# Side_1P.net
KiCad netlist of a schematic drawn in EAGLE
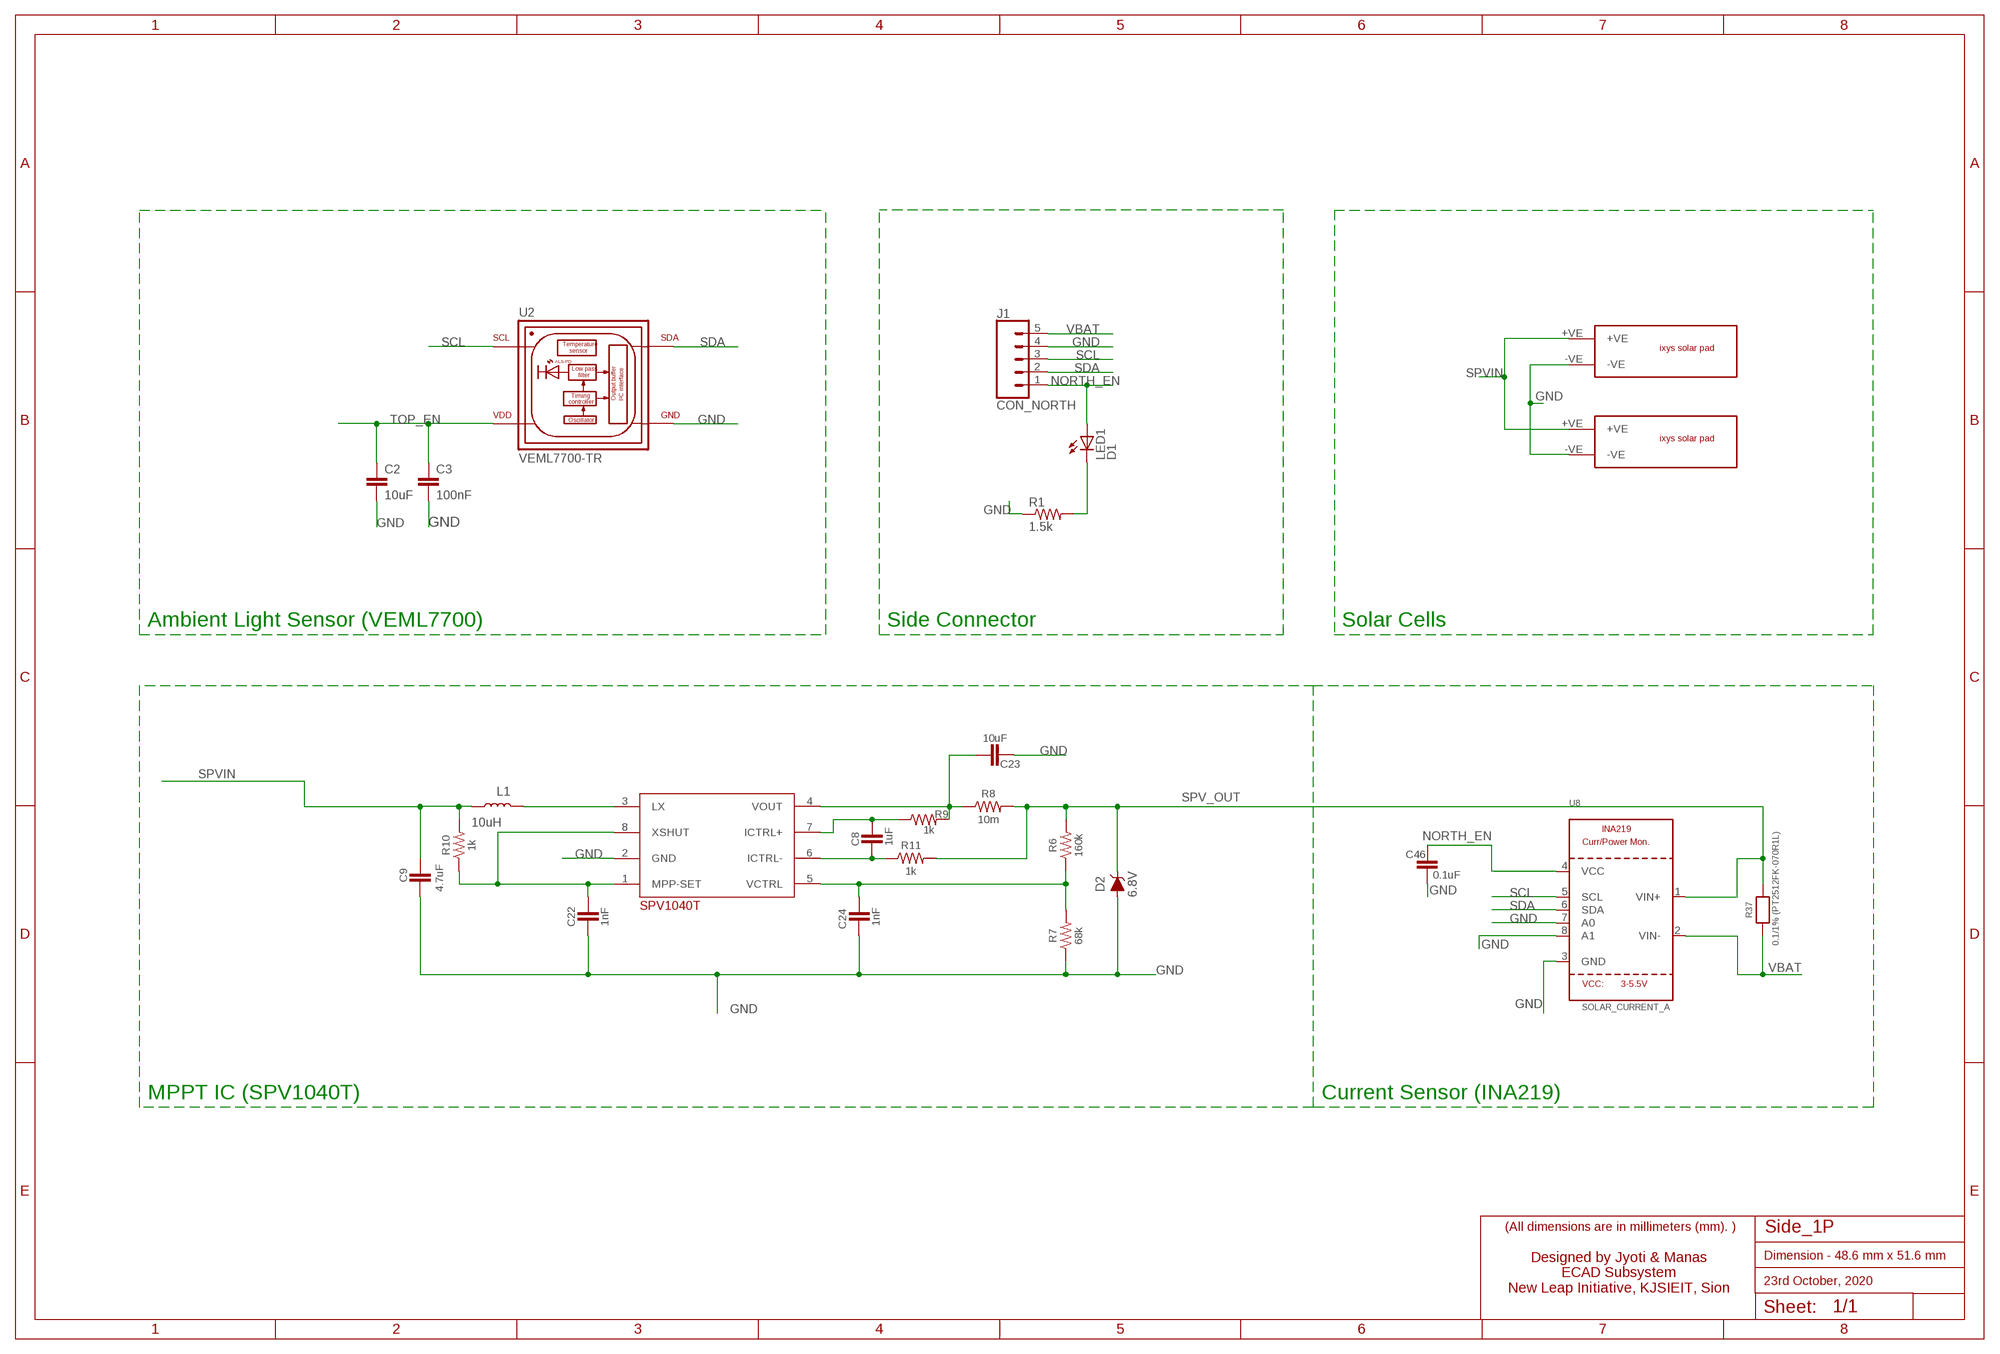
[diagram p0: schematic, sheet 1]

(export (version "E")
  (design (tool "Eeschema 10.0.6"))
  (components
    (comp (ref "C2")
      (value "10uF")
      (footprint "eagle-import:0603")
      (libsource (lib "eagle-import") (part "2.2NF/2200PF-0603-50V-10%"))
    )
    (comp (ref "C3")
      (value "100nF")
      (footprint "eagle-import:0603")
      (libsource (lib "eagle-import") (part "2.2NF/2200PF-0603-50V-10%"))
    )
    (comp (ref "C8")
      (value "1uF")
      (footprint "eagle-import:0603")
      (libsource (lib "eagle-import") (part "10UF-0603-6.3V-20%"))
    )
    (comp (ref "C9")
      (value "4.7uF")
      (footprint "eagle-import:0603")
      (libsource (lib "eagle-import") (part "10UF-0603-6.3V-20%"))
    )
    (comp (ref "C22")
      (value "1nF")
      (footprint "eagle-import:0603")
      (libsource (lib "eagle-import") (part "10UF-0603-6.3V-20%"))
    )
    (comp (ref "C23")
      (value "10uF")
      (footprint "eagle-import:0603")
      (libsource (lib "eagle-import") (part "10UF-0603-6.3V-20%"))
    )
    (comp (ref "C24")
      (value "1nF")
      (footprint "eagle-import:0603")
      (libsource (lib "eagle-import") (part "10UF-0603-6.3V-20%"))
    )
    (comp (ref "C46")
      (value "0.1uF")
      (footprint "eagle-import:0603")
      (libsource (lib "eagle-import") (part "10UF-0603-6.3V-20%"))
    )
    (comp (ref "D2")
      (value "6.8V")
      (footprint "eagle-import:SOD-323")
      (libsource (lib "eagle-import") (part "DIODE-ZENER-MMSZ5232BS"))
    )
    (comp (ref "J1")
      (value "CON_NORTH")
      (footprint "eagle-import:1X05_1.27MM")
      (libsource (lib "eagle-import") (part "CONN_051.27MM"))
    )
    (comp (ref "L1")
      (value "10uH")
      (footprint "eagle-import:0603")
      (libsource (lib "eagle-import") (part "INDUCTOR-0603-33NH"))
    )
    (comp (ref "LED1")
      (value "D1")
      (footprint "eagle-import:CHIP-LED0603")
      (libsource (lib "eagle-import") (part "LEDCHIP-LED0603"))
    )
    (comp (ref "R1")
      (value "1.5k")
      (footprint "eagle-import:R0603")
      (libsource (lib "eagle-import") (part "R-US_R0603"))
    )
    (comp (ref "R6")
      (value "160k")
      (footprint "eagle-import:RES_0603")
      (fields
        (field (name "DIGIKEY_PART_NUMBER") "311-0.0GRTR-ND")
        (field (name "MANUFACTURER") "Yageo")
        (field (name "MPN") "RC0603JR-070RL")
        (field (name "CREATED_BY") "PCBLayout.com")
      )
      (libsource (lib "eagle-import") (part "RC0603JR-070RL"))
    )
    (comp (ref "R7")
      (value "68k")
      (footprint "eagle-import:RES_0603")
      (fields
        (field (name "DIGIKEY_PART_NUMBER") "311-0.0GRTR-ND")
        (field (name "MANUFACTURER") "Yageo")
        (field (name "MPN") "RC0603JR-070RL")
        (field (name "CREATED_BY") "PCBLayout.com")
      )
      (libsource (lib "eagle-import") (part "RC0603JR-070RL"))
    )
    (comp (ref "R8")
      (value "10m")
      (footprint "eagle-import:RES_0603")
      (fields
        (field (name "DIGIKEY_PART_NUMBER") "311-0.0GRTR-ND")
        (field (name "MANUFACTURER") "Yageo")
        (field (name "MPN") "RC0603JR-070RL")
        (field (name "CREATED_BY") "PCBLayout.com")
      )
      (libsource (lib "eagle-import") (part "RC0603JR-070RL"))
    )
    (comp (ref "R9")
      (value "1k")
      (footprint "eagle-import:RES_0603")
      (fields
        (field (name "DIGIKEY_PART_NUMBER") "311-0.0GRTR-ND")
        (field (name "MANUFACTURER") "Yageo")
        (field (name "MPN") "RC0603JR-070RL")
        (field (name "CREATED_BY") "PCBLayout.com")
      )
      (libsource (lib "eagle-import") (part "RC0603JR-070RL"))
    )
    (comp (ref "R10")
      (value "1k")
      (footprint "eagle-import:RES_0603")
      (fields
        (field (name "DIGIKEY_PART_NUMBER") "311-0.0GRTR-ND")
        (field (name "MANUFACTURER") "Yageo")
        (field (name "MPN") "RC0603JR-070RL")
        (field (name "CREATED_BY") "PCBLayout.com")
      )
      (libsource (lib "eagle-import") (part "RC0603JR-070RL"))
    )
    (comp (ref "R11")
      (value "1k")
      (footprint "eagle-import:RES_0603")
      (fields
        (field (name "DIGIKEY_PART_NUMBER") "311-0.0GRTR-ND")
        (field (name "MANUFACTURER") "Yageo")
        (field (name "MPN") "RC0603JR-070RL")
        (field (name "CREATED_BY") "PCBLayout.com")
      )
      (libsource (lib "eagle-import") (part "RC0603JR-070RL"))
    )
    (comp (ref "R37")
      (value "0.1/1% (PT2512FK-070R1L)")
      (footprint "eagle-import:2512")
      (libsource (lib "eagle-import") (part "RESISTOR2512"))
    )
    (comp (ref "SPV_A")
      (value "SPV1040T_")
      (footprint "eagle-import:SOP65P640X120-8N")
      (libsource (lib "eagle-import") (part "SPV1040T_"))
    )
    (comp (ref "U$1")
      (value "IXYS")
      (footprint "eagle-import:IXYS")
      (libsource (lib "eagle-import") (part "IXYS"))
    )
    (comp (ref "U$2")
      (value "IXYS")
      (footprint "eagle-import:IXYS")
      (libsource (lib "eagle-import") (part "IXYS"))
    )
    (comp (ref "U2")
      (value "VEML7700-TR")
      (footprint "eagle-import:XDCR_VEML7700-TR")
      (fields (field (name "DIGI-KEY_PART_NUMBER") "VEML7700CT-ND") (field (name "MF") "Vishay"))
      (libsource (lib "eagle-import") (part "VEML7700-TR"))
    )
    (comp (ref "U8")
      (value "SOLAR_CURRENT_A")
      (footprint "eagle-import:SOT23-8")
      (libsource (lib "eagle-import") (part "INA219"))
    )
  )
  (nets
    (net (code "1") (name "/GND") (class "Default")
      (node (ref "C2") (pin "2") (pinfunction "2_2") (pintype "passive"))
      (node (ref "C22") (pin "2") (pinfunction "2_2") (pintype "passive"))
      (node (ref "C23") (pin "2") (pinfunction "2_2") (pintype "passive"))
      (node (ref "C24") (pin "2") (pinfunction "2_2") (pintype "passive"))
      (node (ref "C3") (pin "2") (pinfunction "2_2") (pintype "passive"))
      (node (ref "C46") (pin "2") (pinfunction "2_2") (pintype "passive"))
      (node (ref "C9") (pin "2") (pinfunction "2_2") (pintype "passive"))
      (node (ref "D2") (pin "A") (pinfunction "A_A") (pintype "passive"))
      (node (ref "J1") (pin "4") (pinfunction "4_4") (pintype "passive"))
      (node (ref "R1") (pin "1") (pinfunction "1_1") (pintype "passive"))
      (node (ref "R7") (pin "1") (pinfunction "1_1") (pintype "passive"))
      (node (ref "SPV_A") (pin "2") (pinfunction "GND_2") (pintype "bidirectional"))
      (node (ref "U$1") (pin "-VE") (pinfunction "-VE_-VE") (pintype "bidirectional"))
      (node (ref "U$2") (pin "-VE") (pinfunction "-VE_-VE") (pintype "bidirectional"))
      (node (ref "U2") (pin "3") (pinfunction "GND_3") (pintype "power_in"))
      (node (ref "U8") (pin "3") (pinfunction "GND_3") (pintype "bidirectional"))
      (node (ref "U8") (pin "7") (pinfunction "A0_7") (pintype "bidirectional"))
      (node (ref "U8") (pin "8") (pinfunction "A1_8") (pintype "bidirectional"))
    )
    (net (code "2") (name "/NORTH_EN") (class "Default")
      (node (ref "C46") (pin "1") (pinfunction "1_1") (pintype "passive"))
      (node (ref "J1") (pin "1") (pinfunction "1_1") (pintype "passive"))
      (node (ref "LED1") (pin "A") (pinfunction "A_A") (pintype "passive"))
      (node (ref "U8") (pin "4") (pinfunction "VCC_4") (pintype "bidirectional"))
    )
    (net (code "3") (name "/SCL") (class "Default")
      (node (ref "J1") (pin "3") (pinfunction "3_3") (pintype "passive"))
      (node (ref "U2") (pin "1") (pinfunction "SCL_1") (pintype "input"))
      (node (ref "U8") (pin "5") (pinfunction "SCL_5") (pintype "bidirectional"))
    )
    (net (code "4") (name "/SDA") (class "Default")
      (node (ref "J1") (pin "2") (pinfunction "2_2") (pintype "passive"))
      (node (ref "U2") (pin "4") (pinfunction "SDA_4") (pintype "bidirectional"))
      (node (ref "U8") (pin "6") (pinfunction "SDA_6") (pintype "bidirectional"))
    )
    (net (code "5") (name "/SPVIN") (class "Default")
      (node (ref "C9") (pin "1") (pinfunction "1_1") (pintype "passive"))
      (node (ref "L1") (pin "1") (pinfunction "1_1") (pintype "passive"))
      (node (ref "R10") (pin "2") (pinfunction "2_2") (pintype "passive"))
      (node (ref "U$1") (pin "+VE") (pinfunction "+VE_+VE") (pintype "bidirectional"))
      (node (ref "U$2") (pin "+VE") (pinfunction "+VE_+VE") (pintype "bidirectional"))
    )
    (net (code "6") (name "/SPV_OUT") (class "Default")
      (node (ref "D2") (pin "C") (pinfunction "C_C") (pintype "passive"))
      (node (ref "R11") (pin "2") (pinfunction "2_2") (pintype "passive"))
      (node (ref "R37") (pin "2") (pinfunction "2_2") (pintype "passive"))
      (node (ref "R6") (pin "2") (pinfunction "2_2") (pintype "passive"))
      (node (ref "R8") (pin "2") (pinfunction "2_2") (pintype "passive"))
      (node (ref "U8") (pin "1") (pinfunction "VIN+_1") (pintype "bidirectional"))
    )
    (net (code "7") (name "/TOP_EN") (class "Default")
      (node (ref "C2") (pin "1") (pinfunction "1_1") (pintype "passive"))
      (node (ref "C3") (pin "1") (pinfunction "1_1") (pintype "passive"))
      (node (ref "U2") (pin "2") (pinfunction "VDD_2") (pintype "power_in"))
    )
    (net (code "8") (name "/VBAT") (class "Default")
      (node (ref "J1") (pin "5") (pinfunction "5_5") (pintype "passive"))
      (node (ref "R37") (pin "1") (pinfunction "1_1") (pintype "passive"))
      (node (ref "U8") (pin "2") (pinfunction "VIN-_2") (pintype "bidirectional"))
    )
    (net (code "9") (name "Net-(LED1-PadC)") (class "Default")
      (node (ref "LED1") (pin "C") (pinfunction "C_C") (pintype "passive"))
      (node (ref "R1") (pin "2") (pinfunction "2_2") (pintype "passive"))
    )
    (net (code "10") (name "Net-(SPV_A-ICTRL+)") (class "Default")
      (node (ref "C8") (pin "1") (pinfunction "1_1") (pintype "passive"))
      (node (ref "R9") (pin "1") (pinfunction "1_1") (pintype "passive"))
      (node (ref "SPV_A") (pin "7") (pinfunction "ICTRL+_7") (pintype "bidirectional"))
    )
    (net (code "11") (name "Net-(SPV_A-ICTRL-)") (class "Default")
      (node (ref "C8") (pin "2") (pinfunction "2_2") (pintype "passive"))
      (node (ref "R11") (pin "1") (pinfunction "1_1") (pintype "passive"))
      (node (ref "SPV_A") (pin "6") (pinfunction "ICTRL-_6") (pintype "bidirectional"))
    )
    (net (code "12") (name "Net-(SPV_A-LX)") (class "Default")
      (node (ref "L1") (pin "2") (pinfunction "2_2") (pintype "passive"))
      (node (ref "SPV_A") (pin "3") (pinfunction "LX_3") (pintype "bidirectional"))
    )
    (net (code "13") (name "Net-(SPV_A-MPP-SET)") (class "Default")
      (node (ref "C22") (pin "1") (pinfunction "1_1") (pintype "passive"))
      (node (ref "R10") (pin "1") (pinfunction "1_1") (pintype "passive"))
      (node (ref "SPV_A") (pin "1") (pinfunction "MPP-SET_1") (pintype "bidirectional"))
      (node (ref "SPV_A") (pin "8") (pinfunction "XSHUT_8") (pintype "bidirectional"))
    )
    (net (code "14") (name "Net-(SPV_A-VCTRL)") (class "Default")
      (node (ref "C24") (pin "1") (pinfunction "1_1") (pintype "passive"))
      (node (ref "R6") (pin "1") (pinfunction "1_1") (pintype "passive"))
      (node (ref "R7") (pin "2") (pinfunction "2_2") (pintype "passive"))
      (node (ref "SPV_A") (pin "5") (pinfunction "VCTRL_5") (pintype "bidirectional"))
    )
    (net (code "15") (name "Net-(SPV_A-VOUT)") (class "Default")
      (node (ref "C23") (pin "1") (pinfunction "1_1") (pintype "passive"))
      (node (ref "R8") (pin "1") (pinfunction "1_1") (pintype "passive"))
      (node (ref "R9") (pin "2") (pinfunction "2_2") (pintype "passive"))
      (node (ref "SPV_A") (pin "4") (pinfunction "VOUT_4") (pintype "bidirectional"))
    )
  )
)
